# DC309A_FTDI_DNI.net
KiCad netlist of a schematic drawn in Altium Designer
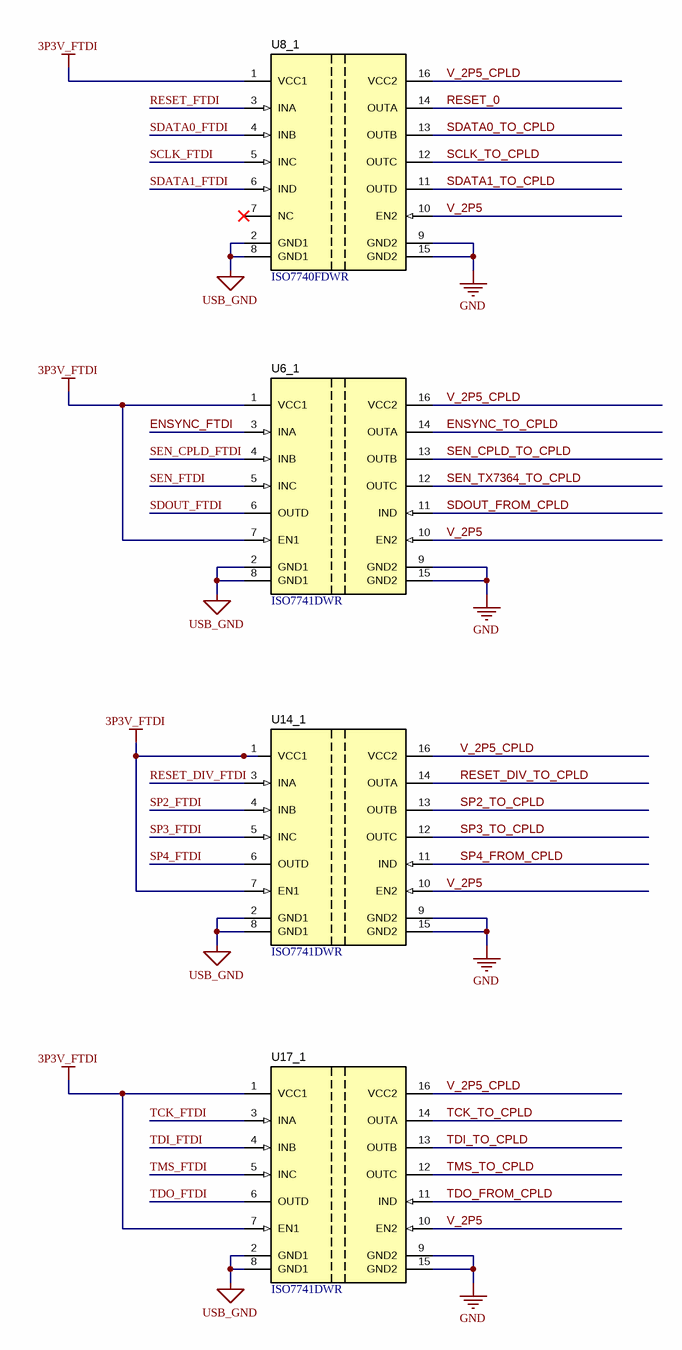
[diagram p0: DC309A_FTDI(DNI).SchDoc]

(export (version "E")
  (design (tool "Eeschema 10.0.6"))
  (components
    (comp (ref "U6_1")
      (value "ISO7741DWR")
      (footprint "DW0016B_HV")
      (description "High-Speed, Low-Power, Robust EMC Quad-Channel Digital Isolator, DW0016B (SOIC-16)")
      (fields
        (field (name "ALTERNATE PARTNUMBER") "ISO7741DW")
        (field (name "MANUFACTURER") "Texas Instruments")
        (field (name "PARTNUMBER") "ISO7741DWR")
      )
      (libsource (lib "Altium Vault - TI") (part "ISO7841"))
    )
    (comp (ref "U8_1")
      (value "ISO7740FDWR")
      (footprint "DW0016B_HV")
      (description "High-Speed, Low-Power, Robust EMC Quad-Channel Digital Isolator, DW0016B (SOIC-16)")
      (fields
        (field (name "ALTERNATE PARTNUMBER") "ISO7740FDW")
        (field (name "PARTNUMBER") "ISO7740FDWR")
        (field (name "MANUFACTURER") "Texas Instruments")
      )
      (libsource (lib "Altium Vault - TI") (part "ISO7740"))
    )
    (comp (ref "U14_1")
      (value "ISO7741DWR")
      (footprint "DW0016B_HV")
      (description "High-Speed, Low-Power, Robust EMC Quad-Channel Digital Isolator, DW0016B (SOIC-16)")
      (fields
        (field (name "ALTERNATE PARTNUMBER") "ISO7741DW")
        (field (name "MANUFACTURER") "Texas Instruments")
        (field (name "PARTNUMBER") "ISO7741DWR")
      )
      (libsource (lib "Altium Vault - TI") (part "ISO7841"))
    )
    (comp (ref "U17_1")
      (value "ISO7741DWR")
      (footprint "DW0016B_HV")
      (description "High-Speed, Low-Power, Robust EMC Quad-Channel Digital Isolator, DW0016B (SOIC-16)")
      (fields
        (field (name "ALTERNATE PARTNUMBER") "ISO7741DW")
        (field (name "MANUFACTURER") "Texas Instruments")
        (field (name "PARTNUMBER") "ISO7741DWR")
      )
      (libsource (lib "Altium Vault - TI") (part "ISO7841"))
    )
  )
  (nets
    (net (code "1") (name "/ENSYNC_FTDI") (class "Default")
      (node (ref "U6_1") (pin "3") (pinfunction "INA_3") (pintype "input"))
    )
    (net (code "2") (name "/ENSYNC_TO_CPLD") (class "Default")
      (node (ref "U6_1") (pin "14") (pinfunction "OUTA_14") (pintype "tri_state"))
    )
    (net (code "3") (name "/RESET_0") (class "Default")
      (node (ref "U8_1") (pin "14") (pinfunction "OUTA_14") (pintype "tri_state"))
    )
    (net (code "4") (name "/RESET_DIV_FTDI") (class "Default")
      (node (ref "U14_1") (pin "3") (pinfunction "INA_3") (pintype "input"))
    )
    (net (code "5") (name "/RESET_DIV_TO_CPLD") (class "Default")
      (node (ref "U14_1") (pin "14") (pinfunction "OUTA_14") (pintype "tri_state"))
    )
    (net (code "6") (name "/RESET_FTDI") (class "Default")
      (node (ref "U8_1") (pin "3") (pinfunction "INA_3") (pintype "input"))
    )
    (net (code "7") (name "/SCLK_FTDI") (class "Default")
      (node (ref "U8_1") (pin "5") (pinfunction "INC_5") (pintype "input"))
    )
    (net (code "8") (name "/SCLK_TO_CPLD") (class "Default")
      (node (ref "U8_1") (pin "12") (pinfunction "OUTC_12") (pintype "tri_state"))
    )
    (net (code "9") (name "/SDATA0_FTDI") (class "Default")
      (node (ref "U8_1") (pin "4") (pinfunction "INB_4") (pintype "input"))
    )
    (net (code "10") (name "/SDATA0_TO_CPLD") (class "Default")
      (node (ref "U8_1") (pin "13") (pinfunction "OUTB_13") (pintype "tri_state"))
    )
    (net (code "11") (name "/SDATA1_FTDI") (class "Default")
      (node (ref "U8_1") (pin "6") (pinfunction "IND_6") (pintype "input"))
    )
    (net (code "12") (name "/SDATA1_TO_CPLD") (class "Default")
      (node (ref "U8_1") (pin "11") (pinfunction "OUTD_11") (pintype "tri_state"))
    )
    (net (code "13") (name "/SDOUT_FROM_CPLD") (class "Default")
      (node (ref "U6_1") (pin "11") (pinfunction "IND_11") (pintype "input"))
    )
    (net (code "14") (name "/SDOUT_FTDI") (class "Default")
      (node (ref "U6_1") (pin "6") (pinfunction "OUTD_6") (pintype "tri_state"))
    )
    (net (code "15") (name "/SEN_CPLD_FTDI") (class "Default")
      (node (ref "U6_1") (pin "4") (pinfunction "INB_4") (pintype "input"))
    )
    (net (code "16") (name "/SEN_CPLD_TO_CPLD") (class "Default")
      (node (ref "U6_1") (pin "13") (pinfunction "OUTB_13") (pintype "tri_state"))
    )
    (net (code "17") (name "/SEN_FTDI") (class "Default")
      (node (ref "U6_1") (pin "5") (pinfunction "INC_5") (pintype "input"))
    )
    (net (code "18") (name "/SEN_TX7364_TO_CPLD") (class "Default")
      (node (ref "U6_1") (pin "12") (pinfunction "OUTC_12") (pintype "tri_state"))
    )
    (net (code "19") (name "/SP2_FTDI") (class "Default")
      (node (ref "U14_1") (pin "4") (pinfunction "INB_4") (pintype "input"))
    )
    (net (code "20") (name "/SP2_TO_CPLD") (class "Default")
      (node (ref "U14_1") (pin "13") (pinfunction "OUTB_13") (pintype "tri_state"))
    )
    (net (code "21") (name "/SP3_FTDI") (class "Default")
      (node (ref "U14_1") (pin "5") (pinfunction "INC_5") (pintype "input"))
    )
    (net (code "22") (name "/SP3_TO_CPLD") (class "Default")
      (node (ref "U14_1") (pin "12") (pinfunction "OUTC_12") (pintype "tri_state"))
    )
    (net (code "23") (name "/SP4_FROM_CPLD") (class "Default")
      (node (ref "U14_1") (pin "11") (pinfunction "IND_11") (pintype "input"))
    )
    (net (code "24") (name "/SP4_FTDI") (class "Default")
      (node (ref "U14_1") (pin "6") (pinfunction "OUTD_6") (pintype "tri_state"))
    )
    (net (code "25") (name "/TCK_FTDI") (class "Default")
      (node (ref "U17_1") (pin "3") (pinfunction "INA_3") (pintype "input"))
    )
    (net (code "26") (name "/TCK_TO_CPLD") (class "Default")
      (node (ref "U17_1") (pin "14") (pinfunction "OUTA_14") (pintype "tri_state"))
    )
    (net (code "27") (name "/TDI_FTDI") (class "Default")
      (node (ref "U17_1") (pin "4") (pinfunction "INB_4") (pintype "input"))
    )
    (net (code "28") (name "/TDI_TO_CPLD") (class "Default")
      (node (ref "U17_1") (pin "13") (pinfunction "OUTB_13") (pintype "tri_state"))
    )
    (net (code "29") (name "/TDO_FROM_CPLD") (class "Default")
      (node (ref "U17_1") (pin "11") (pinfunction "IND_11") (pintype "input"))
    )
    (net (code "30") (name "/TDO_FTDI") (class "Default")
      (node (ref "U17_1") (pin "6") (pinfunction "OUTD_6") (pintype "tri_state"))
    )
    (net (code "31") (name "/TMS_FTDI") (class "Default")
      (node (ref "U17_1") (pin "5") (pinfunction "INC_5") (pintype "input"))
    )
    (net (code "32") (name "/TMS_TO_CPLD") (class "Default")
      (node (ref "U17_1") (pin "12") (pinfunction "OUTC_12") (pintype "tri_state"))
    )
    (net (code "33") (name "/V_2P5") (class "Default")
      (node (ref "U14_1") (pin "10") (pinfunction "EN2_10") (pintype "input"))
      (node (ref "U17_1") (pin "10") (pinfunction "EN2_10") (pintype "input"))
      (node (ref "U6_1") (pin "10") (pinfunction "EN2_10") (pintype "input"))
      (node (ref "U8_1") (pin "10") (pinfunction "EN2_10") (pintype "input"))
    )
    (net (code "34") (name "/V_2P5_CPLD") (class "Default")
      (node (ref "U14_1") (pin "16") (pinfunction "VCC2_16") (pintype "power_in"))
      (node (ref "U17_1") (pin "16") (pinfunction "VCC2_16") (pintype "power_in"))
      (node (ref "U6_1") (pin "16") (pinfunction "VCC2_16") (pintype "power_in"))
      (node (ref "U8_1") (pin "16") (pinfunction "VCC2_16") (pintype "power_in"))
    )
    (net (code "35") (name "3P3V_FTDI") (class "Default")
      (node (ref "U14_1") (pin "1") (pinfunction "VCC1_1") (pintype "power_in"))
      (node (ref "U14_1") (pin "7") (pinfunction "EN1_7") (pintype "input"))
      (node (ref "U17_1") (pin "1") (pinfunction "VCC1_1") (pintype "power_in"))
      (node (ref "U17_1") (pin "7") (pinfunction "EN1_7") (pintype "input"))
      (node (ref "U6_1") (pin "1") (pinfunction "VCC1_1") (pintype "power_in"))
      (node (ref "U6_1") (pin "7") (pinfunction "EN1_7") (pintype "input"))
      (node (ref "U8_1") (pin "1") (pinfunction "VCC1_1") (pintype "power_in"))
    )
    (net (code "36") (name "GND") (class "Default")
      (node (ref "U14_1") (pin "15") (pinfunction "GND2_15") (pintype "power_in"))
      (node (ref "U14_1") (pin "9") (pinfunction "GND2_9") (pintype "power_in"))
      (node (ref "U17_1") (pin "15") (pinfunction "GND2_15") (pintype "power_in"))
      (node (ref "U17_1") (pin "9") (pinfunction "GND2_9") (pintype "power_in"))
      (node (ref "U6_1") (pin "15") (pinfunction "GND2_15") (pintype "power_in"))
      (node (ref "U6_1") (pin "9") (pinfunction "GND2_9") (pintype "power_in"))
      (node (ref "U8_1") (pin "15") (pinfunction "GND2_15") (pintype "power_in"))
      (node (ref "U8_1") (pin "9") (pinfunction "GND2_9") (pintype "power_in"))
    )
    (net (code "37") (name "USB_GND") (class "Default")
      (node (ref "U14_1") (pin "2") (pinfunction "GND1_2") (pintype "power_in"))
      (node (ref "U14_1") (pin "8") (pinfunction "GND1_8") (pintype "power_in"))
      (node (ref "U17_1") (pin "2") (pinfunction "GND1_2") (pintype "power_in"))
      (node (ref "U17_1") (pin "8") (pinfunction "GND1_8") (pintype "power_in"))
      (node (ref "U6_1") (pin "2") (pinfunction "GND1_2") (pintype "power_in"))
      (node (ref "U6_1") (pin "8") (pinfunction "GND1_8") (pintype "power_in"))
      (node (ref "U8_1") (pin "2") (pinfunction "GND1_2") (pintype "power_in"))
      (node (ref "U8_1") (pin "8") (pinfunction "GND1_8") (pintype "power_in"))
    )
    (net (code "38") (name "unconnected-(U8_1-NC-Pad7)") (class "Default")
      (node (ref "U8_1") (pin "7") (pinfunction "NC_7") (pintype "passive+no_connect"))
    )
  )
)
